# BAR_SENS.net
KiCad netlist of a schematic drawn in Altium Designer
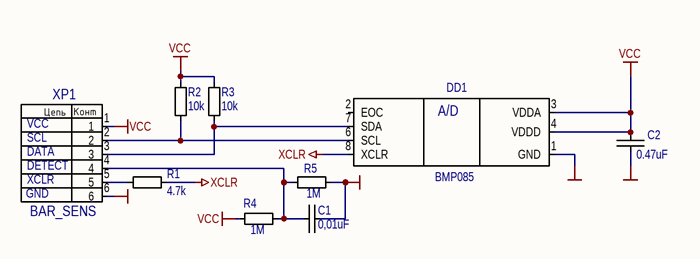
[diagram p0: BAR_SENS.SchDoc]

(export (version "E")
  (design (tool "Eeschema 10.0.6"))
  (components
    (comp (ref "C1")
      (value "0,01uF")
      (footprint "Cap_0805")
      (fields (field (name "MANUFACTURER") "AVX") (field (name "PART NUMBER") "08055C103JAT2A"))
      (libsource (lib "PANEL") (part "Cap_0805"))
    )
    (comp (ref "C2")
      (value "0.47uF")
      (footprint "Cap_0805")
      (fields (field (name "MANUFACTURER") "AVX") (field (name "PART NUMBER") "0805YC475KAT2A"))
      (libsource (lib "PANEL") (part "Cap_0805"))
    )
    (comp (ref "DD1") (value "BMP085") (footprint "BMP085") (libsource (lib "BAR_SENS") (part "BMP085")))
    (comp (ref "R1")
      (value "4.7k")
      (footprint "Res_0805")
      (fields (field (name "MANUFACTURER") "Vishay"))
      (libsource (lib "PANEL") (part "Res_0805"))
    )
    (comp (ref "R2")
      (value "10k")
      (footprint "Res_0805")
      (fields (field (name "MANUFACTURER") "Vishay"))
      (libsource (lib "") (part "Res_0805_1"))
    )
    (comp (ref "R3")
      (value "10k")
      (footprint "Res_0805")
      (fields (field (name "MANUFACTURER") "Vishay"))
      (libsource (lib "") (part "Res_0805_1"))
    )
    (comp (ref "R4")
      (value "1M")
      (footprint "Res_0805")
      (fields (field (name "MANUFACTURER") "Vishay"))
      (libsource (lib "PANEL") (part "Res_0805"))
    )
    (comp (ref "R5")
      (value "1M")
      (footprint "Res_0805")
      (fields (field (name "MANUFACTURER") "Vishay"))
      (libsource (lib "PANEL") (part "Res_0805"))
    )
    (comp (ref "XP1")
      (value "BAR_SENS")
      (footprint "SENS_LEGS")
      (libsource (lib "BAR_SENS") (part "BAR_SENS"))
    )
  )
  (nets
    (net (code "1") (name "GND") (class "Default")
      (node (ref "C1") (pin "2") (pinfunction "2_2") (pintype "passive"))
      (node (ref "C2") (pin "1") (pinfunction "1_1") (pintype "passive"))
      (node (ref "DD1") (pin "1") (pinfunction "GND_1") (pintype "passive"))
      (node (ref "R5") (pin "1") (pinfunction "1_1") (pintype "passive"))
      (node (ref "XP1") (pin "6") (pinfunction "6_6") (pintype "passive"))
    )
    (net (code "2") (name "Net-(C1-Pad1)") (class "Default")
      (node (ref "C1") (pin "1") (pinfunction "1_1") (pintype "passive"))
      (node (ref "R4") (pin "1") (pinfunction "1_1") (pintype "passive"))
      (node (ref "R5") (pin "2") (pinfunction "2_2") (pintype "passive"))
      (node (ref "XP1") (pin "4") (pinfunction "4_4") (pintype "passive"))
    )
    (net (code "3") (name "Net-(DD1-SCL)") (class "Default")
      (node (ref "DD1") (pin "6") (pinfunction "SCL_6") (pintype "passive"))
      (node (ref "R2") (pin "2") (pinfunction "2_2") (pintype "passive"))
      (node (ref "XP1") (pin "2") (pinfunction "2_2") (pintype "passive"))
    )
    (net (code "4") (name "Net-(DD1-SDA)") (class "Default")
      (node (ref "DD1") (pin "7") (pinfunction "SDA_7") (pintype "passive"))
      (node (ref "R3") (pin "2") (pinfunction "2_2") (pintype "passive"))
      (node (ref "XP1") (pin "3") (pinfunction "3_3") (pintype "passive"))
    )
    (net (code "5") (name "Net-(R1-Pad2)") (class "Default")
      (node (ref "R1") (pin "2") (pinfunction "2_2") (pintype "passive"))
      (node (ref "XP1") (pin "5") (pinfunction "5_5") (pintype "passive"))
    )
    (net (code "6") (name "VCC") (class "Default")
      (node (ref "C2") (pin "2") (pinfunction "2_2") (pintype "passive"))
      (node (ref "DD1") (pin "3") (pinfunction "VDDA_3") (pintype "passive"))
      (node (ref "DD1") (pin "4") (pinfunction "VDDD_4") (pintype "passive"))
      (node (ref "R2") (pin "1") (pinfunction "1_1") (pintype "passive"))
      (node (ref "R3") (pin "1") (pinfunction "1_1") (pintype "passive"))
      (node (ref "R4") (pin "2") (pinfunction "2_2") (pintype "passive"))
      (node (ref "XP1") (pin "1") (pinfunction "1_1") (pintype "passive"))
    )
    (net (code "7") (name "XCLR") (class "Default")
      (node (ref "DD1") (pin "8") (pinfunction "XCLR_8") (pintype "passive"))
      (node (ref "R1") (pin "1") (pinfunction "1_1") (pintype "passive"))
    )
    (net (code "8") (name "unconnected-(DD1-EOC-Pad2)") (class "Default")
      (node (ref "DD1") (pin "2") (pinfunction "EOC_2") (pintype "passive"))
    )
  )
)
